# design.net
KiCad netlist of a schematic drawn in Altium Designer
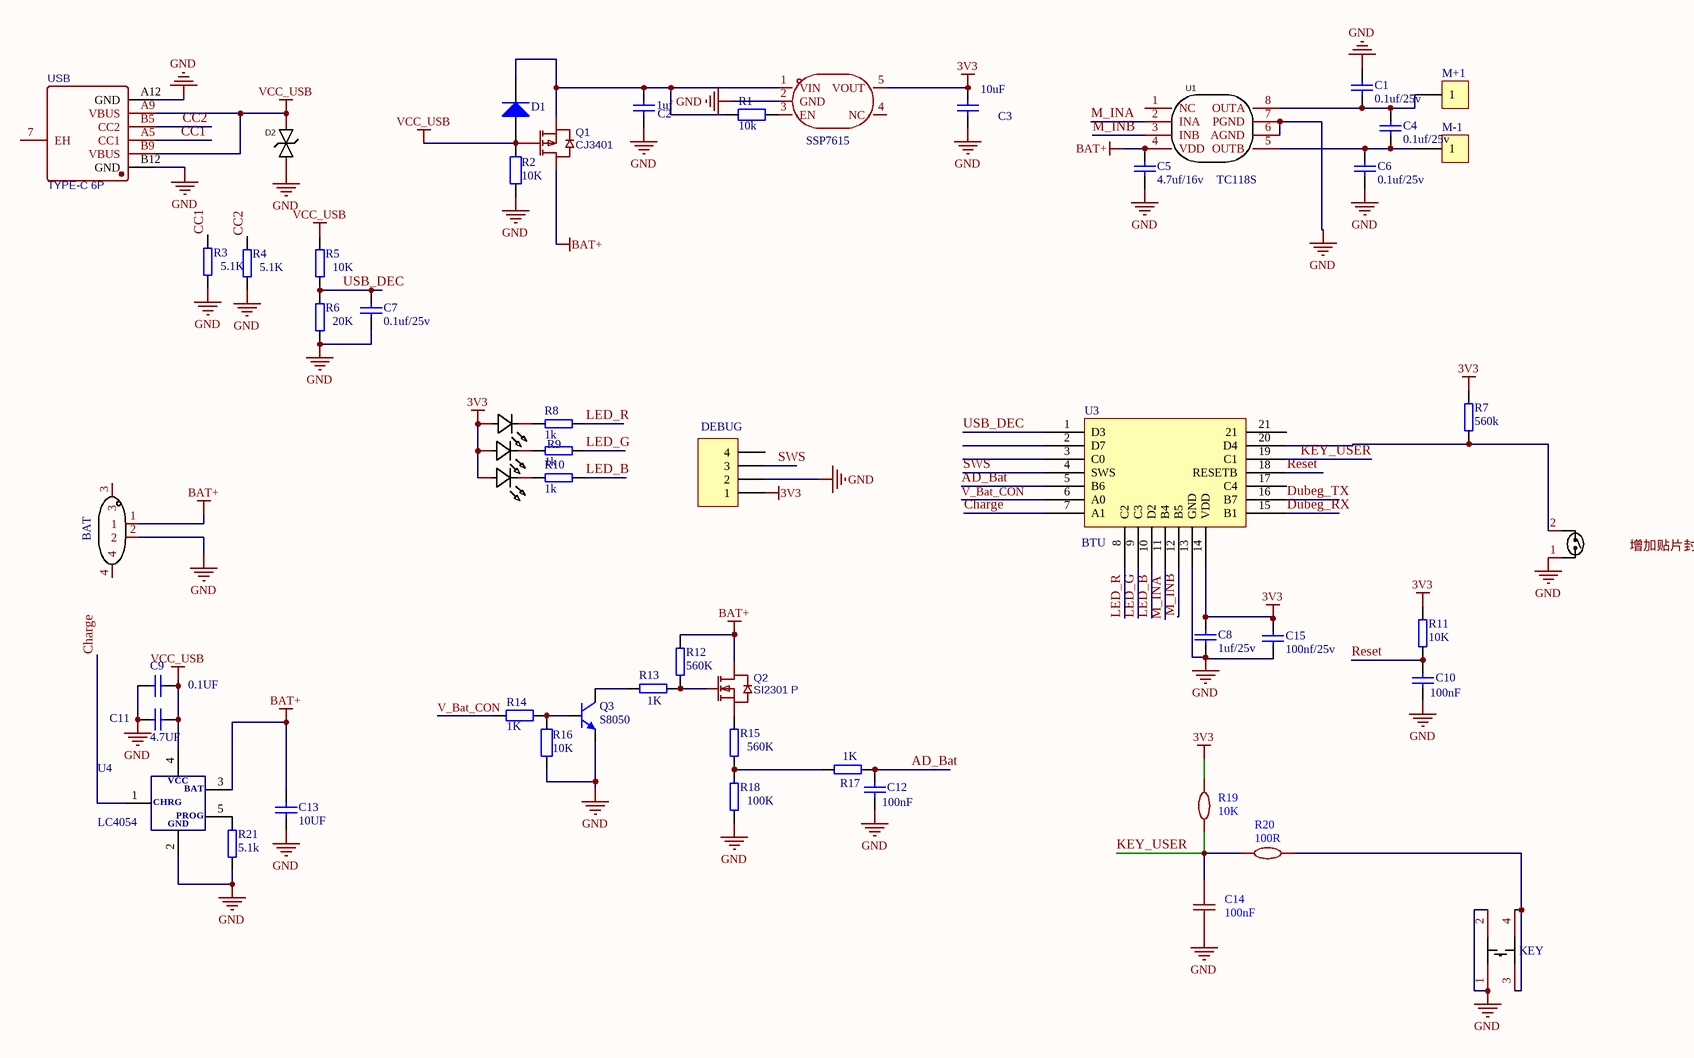
[diagram p0: 滚动足球球蓝牙款.SchDoc]

(export (version "E")
  (design (tool "Eeschema 10.0.6"))
  (components
    (comp (ref "C1")
      (value "0.1uf/25v")
      (footprint "0603_C")
      (description "Capacitor")
      (fields (field (name "PUBLISHER") "Altium Limited"))
      (libsource (lib "*") (part "Cap"))
    )
    (comp (ref "C2")
      (value "1uf")
      (footprint "0603_C")
      (description "无极电容")
      (libsource (lib "电容电阻电感保险") (part "Cap1"))
    )
    (comp (ref "C3")
      (value "10uF")
      (footprint "0603_C")
      (description "Capacitor")
      (fields (field (name "PUBLISHER") "Altium Limited"))
      (libsource (lib "*") (part "Cap"))
    )
    (comp (ref "C4")
      (value "0.1uf/25v")
      (footprint "0603_C")
      (description "Capacitor")
      (fields (field (name "PUBLISHER") "Altium Limited"))
      (libsource (lib "*") (part "Cap"))
    )
    (comp (ref "C5")
      (value "4.7uf/16v")
      (footprint "0805_C")
      (description "Capacitor")
      (fields (field (name "PUBLISHER") "Altium Limited"))
      (libsource (lib "*") (part "Cap"))
    )
    (comp (ref "C6")
      (value "0.1uf/25v")
      (footprint "0603_C")
      (description "Capacitor")
      (fields (field (name "PUBLISHER") "Altium Limited"))
      (libsource (lib "*") (part "Cap"))
    )
    (comp (ref "C7")
      (value "0.1uf/25v")
      (footprint "0603_C")
      (description "Capacitor")
      (fields (field (name "PUBLISHER") "Altium Limited"))
      (libsource (lib "*") (part "Cap"))
    )
    (comp (ref "C8")
      (value "1uf/25v")
      (footprint "0603_C")
      (description "Capacitor")
      (fields (field (name "PUBLISHER") "Altium Limited"))
      (libsource (lib "*") (part "Cap"))
    )
    (comp (ref "C9") (value "0.1UF") (footprint "0603_c") (libsource (lib "DIY") (part "CAP")))
    (comp (ref "C10") (value "100nF") (footprint "0603_C") (libsource (lib "DIY") (part "CAP")))
    (comp (ref "C11") (value "4.7UF") (footprint "0603_c") (libsource (lib "DIY") (part "CAP")))
    (comp (ref "C12") (value "100nF") (footprint "0603_C") (libsource (lib "DIY") (part "CAP")))
    (comp (ref "C13") (value "10UF") (footprint "0603_C") (libsource (lib "DIY") (part "CAP")))
    (comp (ref "C14")
      (value "100nF")
      (footprint "0603_c")
      (libsource (lib "altium-import") (part "root_1_CAP_0603_"))
    )
    (comp (ref "C15")
      (value "100nf/25v")
      (footprint "0603_C")
      (description "Capacitor")
      (fields (field (name "PUBLISHER") "Altium Limited"))
      (libsource (lib "*") (part "Cap"))
    )
    (comp (ref "CN1")
      (value "BAT")
      (footprint "CONN-SMD_1.25-2PWT")
      (fields (field (name "MANUFACTURER PART") "HC-1.25-2PLT"))
      (libsource (lib "altium-import") (part "root_0_mirrored_HC-1.25-2PLT_"))
    )
    (comp (ref "D1")
      (value "~")
      (footprint "SOD-123FL")
      (description "High Conductance Fast Diode")
      (fields (field (name "PUBLISHER") "Altium Limited"))
      (libsource (lib "Miscellaneous Devices") (part "Diode 1N4148"))
    )
    (comp (ref "D2")
      (value "SMF5.0CA_C726939")
      (footprint "SOD-123 双向")
      (fields (field (name "MANUFACTURER PART") "SMF5.0CA"))
      (libsource (lib "altium-import") (part "root_1_SMF5.0CA_C726939_"))
    )
    (comp (ref "K1")
      (value "KEY")
      (footprint "SW-SMD_4P-L4.5-W4.5-P3.00-LS7.0")
      (fields (field (name "MANUFACTURER PART") "TS-1002S-05026C"))
      (libsource (lib "altium-import") (part "root_1_TS-1002S-05026C_"))
    )
    (comp (ref "LED1")
      (value "S6-3528RGBTA")
      (footprint "LED-SMD-6P_S6-3528RGBTA")
      (libsource (lib "altium-import") (part "root_0_S6-3528RGBTA_"))
    )
    (comp (ref "M+1") (value "~") (footprint "PAD2") (libsource (lib "zzh-sch") (part "CON1")))
    (comp (ref "M-1") (value "~") (footprint "PAD2") (libsource (lib "zzh-sch") (part "CON1")))
    (comp (ref "P1")
      (value "DEBUG")
      (footprint "SIP4-2.54")
      (description "Header, 4-Pin")
      (fields (field (name "PUBLISHER") "Altium Limited"))
      (libsource (lib "Miscellaneous Connectors") (part "Header 4"))
    )
    (comp (ref "Q1")
      (value "CJ3401")
      (footprint "SOT-23")
      (fields (field (name "BOM_SUPPLIER PART") "C13799"))
      (libsource (lib "altium-import") (part "root_2_mirrored_CJ3401_"))
    )
    (comp (ref "Q2")
      (value "SI2301 P")
      (footprint "SOT-23")
      (fields
        (field (name "BOM_SUPPLIER PART") "C2890442")
        (field (name "BOM_MANUFACTURER PART") "JMTL3400A")
        (field (name "CONTRIBUTOR") "LCSC")
      )
      (libsource (lib "altium-import") (part "root_0_JMTL3400A_"))
    )
    (comp (ref "Q3")
      (value "S8050")
      (footprint "SOT-23(SOT-23-3)")
      (description "NPN三极管")
      (libsource (lib "二三极管mos可控硅") (part "NPN_sot23"))
    )
    (comp (ref "R1")
      (value "10k")
      (footprint "0603_R")
      (description "Resistor")
      (fields (field (name "PUBLISHER") "Altium Limited"))
      (libsource (lib "") (part "Res2_1"))
    )
    (comp (ref "R2")
      (value "10K")
      (footprint "0603_R")
      (description "Resistor")
      (fields (field (name "PUBLISHER") "Altium Limited"))
      (libsource (lib "") (part "Res2_2"))
    )
    (comp (ref "R3") (value "5.1K") (footprint "0603_R") (libsource (lib "DIY") (part "RES")))
    (comp (ref "R4") (value "5.1K") (footprint "0603_R") (libsource (lib "DIY") (part "RES")))
    (comp (ref "R5") (value "10K") (footprint "0603_R") (libsource (lib "DIY") (part "RES")))
    (comp (ref "R6") (value "20K") (footprint "0603_R") (libsource (lib "DIY") (part "RES")))
    (comp (ref "R7") (value "560k") (footprint "0603_R") (libsource (lib "DIY") (part "RES")))
    (comp (ref "R8") (value "1k") (footprint "0603_R") (libsource (lib "DIY") (part "RES")))
    (comp (ref "R9") (value "1k") (footprint "0603_R") (libsource (lib "DIY") (part "RES")))
    (comp (ref "R10") (value "1k") (footprint "0603_R") (libsource (lib "DIY") (part "RES")))
    (comp (ref "R11") (value "10K") (footprint "0603_R") (libsource (lib "DIY") (part "RES")))
    (comp (ref "R12") (value "560K") (footprint "0603_R") (libsource (lib "") (part "RES_1")))
    (comp (ref "R13") (value "1K") (footprint "0603_R") (libsource (lib "*") (part "RES")))
    (comp (ref "R14")
      (value "1K")
      (footprint "0603_r")
      (description "Resistor")
      (fields (field (name "PUBLISHER") "Altium Limited"))
      (libsource (lib "*") (part "Res2"))
    )
    (comp (ref "R15") (value "560K") (footprint "0603_R") (libsource (lib "DIY") (part "RES")))
    (comp (ref "R16")
      (value "10K")
      (footprint "0603_r")
      (description "Resistor")
      (fields (field (name "PUBLISHER") "Altium Limited"))
      (libsource (lib "") (part "Res2_1"))
    )
    (comp (ref "R17") (value "1K") (footprint "0603_R") (libsource (lib "DIY") (part "RES")))
    (comp (ref "R18") (value "100K") (footprint "0603_R") (libsource (lib "DIY") (part "RES")))
    (comp (ref "R19")
      (value "10K")
      (footprint "0603_R")
      (libsource (lib "altium-import") (part "root_1_Res_0603_"))
    )
    (comp (ref "R20")
      (value "100R")
      (footprint "0603_R")
      (libsource (lib "altium-import") (part "root_2_Res_0603_"))
    )
    (comp (ref "R21") (value "5.1k") (footprint "0603_R") (libsource (lib "DIY") (part "RES")))
    (comp (ref "SW1")
      (value "SW-18010P")
      (footprint "SMD-X160")
      (libsource (lib "altium-import") (part "root_0_SW-18010P_"))
    )
    (comp (ref "U1")
      (value "TC118S")
      (footprint "SOP8")
      (libsource (lib "altium-import") (part "root_0_TC118S_"))
    )
    (comp (ref "U2")
      (value "SSP7615")
      (footprint "SOT-23-5")
      (libsource (lib "altium-import") (part "root_0_SSP7615-33M5R_"))
    )
    (comp (ref "U3") (value "BTU") (footprint "BTU") (libsource (lib "MyLib") (part "BTU")))
    (comp (ref "U4") (value "LC4054") (footprint "SOT-23-5") (libsource (lib "DIY") (part "LTC4054")))
    (comp (ref "USB")
      (value "TYPE-C 6P")
      (footprint "TPYE-C-6")
      (fields (field (name "BOM_SUPPLIER PART") "C456012") (field (name "CONTRIBUTOR") "LCSC"))
      (libsource (lib "altium-import") (part "root_2_TYPE-C 6P_"))
    )
  )
  (nets
    (net (code "1") (name "/AD_Bat") (class "Default")
      (node (ref "C12") (pin "2") (pintype "passive"))
      (node (ref "R17") (pin "1") (pinfunction "1_1") (pintype "passive"))
      (node (ref "U3") (pin "5") (pinfunction "B6_5") (pintype "passive"))
    )
    (net (code "2") (name "/CC1") (class "Default")
      (node (ref "R3") (pin "1") (pinfunction "1_1") (pintype "passive"))
      (node (ref "USB") (pin "A5") (pinfunction "CC1_A5") (pintype "passive"))
    )
    (net (code "3") (name "/CC2") (class "Default")
      (node (ref "R4") (pin "1") (pinfunction "1_1") (pintype "passive"))
      (node (ref "USB") (pin "B5") (pinfunction "CC2_B5") (pintype "passive"))
    )
    (net (code "4") (name "/Charge") (class "Default")
      (node (ref "U3") (pin "7") (pinfunction "A1_7") (pintype "passive"))
      (node (ref "U4") (pin "1") (pinfunction "1_1") (pintype "passive"))
    )
    (net (code "5") (name "/Dubeg_RX") (class "Default")
      (node (ref "U3") (pin "15") (pinfunction "B1_15") (pintype "passive"))
    )
    (net (code "6") (name "/Dubeg_TX") (class "Default")
      (node (ref "U3") (pin "16") (pinfunction "B7_16") (pintype "passive"))
    )
    (net (code "7") (name "/KEY_USER") (class "Default")
      (node (ref "C14") (pin "2") (pinfunction "2_2") (pintype "passive"))
      (node (ref "R19") (pin "1") (pinfunction "1_1") (pintype "passive"))
      (node (ref "R20") (pin "2") (pinfunction "2_2") (pintype "passive"))
      (node (ref "U3") (pin "19") (pinfunction "C1_19") (pintype "passive"))
    )
    (net (code "8") (name "/LED_B") (class "Default")
      (node (ref "R10") (pin "2") (pinfunction "2_2") (pintype "passive"))
      (node (ref "U3") (pin "10") (pinfunction "D2_10") (pintype "passive"))
    )
    (net (code "9") (name "/LED_G") (class "Default")
      (node (ref "R9") (pin "2") (pinfunction "2_2") (pintype "passive"))
      (node (ref "U3") (pin "9") (pinfunction "C3_9") (pintype "passive"))
    )
    (net (code "10") (name "/LED_R") (class "Default")
      (node (ref "R8") (pin "2") (pinfunction "2_2") (pintype "passive"))
      (node (ref "U3") (pin "8") (pinfunction "C2_8") (pintype "passive"))
    )
    (net (code "11") (name "/M_INA") (class "Default")
      (node (ref "U1") (pin "2") (pinfunction "INA_2") (pintype "passive"))
      (node (ref "U3") (pin "11") (pinfunction "B4_11") (pintype "passive"))
    )
    (net (code "12") (name "/M_INB") (class "Default")
      (node (ref "U1") (pin "3") (pinfunction "INB_3") (pintype "passive"))
      (node (ref "U3") (pin "12") (pinfunction "B5_12") (pintype "passive"))
    )
    (net (code "13") (name "/Reset") (class "Default")
      (node (ref "C10") (pin "2") (pintype "passive"))
      (node (ref "R11") (pin "2") (pinfunction "2_2") (pintype "passive"))
      (node (ref "U3") (pin "18") (pinfunction "RESETB_18") (pintype "passive"))
    )
    (net (code "14") (name "/SWS") (class "Default")
      (node (ref "P1") (pin "3") (pinfunction "3_3") (pintype "passive"))
      (node (ref "U3") (pin "4") (pinfunction "SWS_4") (pintype "passive"))
    )
    (net (code "15") (name "/USB_DEC") (class "Default")
      (node (ref "C7") (pin "2") (pinfunction "2_2") (pintype "passive"))
      (node (ref "R5") (pin "2") (pinfunction "2_2") (pintype "passive"))
      (node (ref "R6") (pin "1") (pinfunction "1_1") (pintype "passive"))
      (node (ref "U3") (pin "1") (pinfunction "D3_1") (pintype "passive"))
    )
    (net (code "16") (name "/V_Bat_CON") (class "Default")
      (node (ref "R14") (pin "2") (pinfunction "2_2") (pintype "passive"))
      (node (ref "U3") (pin "6") (pinfunction "A0_6") (pintype "passive"))
    )
    (net (code "18") (name "3V3") (class "Default")
      (node (ref "C15") (pin "2") (pinfunction "2_2") (pintype "passive"))
      (node (ref "C3") (pin "2") (pinfunction "2_2") (pintype "passive"))
      (node (ref "C8") (pin "2") (pinfunction "2_2") (pintype "passive"))
      (node (ref "LED1") (pin "4") (pinfunction "4_4") (pintype "passive"))
      (node (ref "LED1") (pin "5") (pinfunction "5_5") (pintype "passive"))
      (node (ref "LED1") (pin "6") (pinfunction "6_6") (pintype "passive"))
      (node (ref "P1") (pin "1") (pinfunction "1_1") (pintype "passive"))
      (node (ref "R11") (pin "1") (pinfunction "1_1") (pintype "passive"))
      (node (ref "R19") (pin "2") (pinfunction "2_2") (pintype "passive"))
      (node (ref "R7") (pin "2") (pinfunction "2_2") (pintype "passive"))
      (node (ref "U2") (pin "5") (pinfunction "VOUT_5") (pintype "passive"))
      (node (ref "U3") (pin "14") (pinfunction "VDD_14") (pintype "passive"))
    )
    (net (code "19") (name "BAT+") (class "Default")
      (node (ref "C13") (pin "2") (pintype "passive"))
      (node (ref "C5") (pin "1") (pinfunction "1_1") (pintype "passive"))
      (node (ref "CN1") (pin "1") (pinfunction "1_1") (pintype "passive"))
      (node (ref "Q1") (pin "3") (pinfunction "D_3") (pintype "passive"))
      (node (ref "Q2") (pin "2") (pinfunction "D_2") (pintype "passive"))
      (node (ref "R12") (pin "1") (pintype "passive"))
      (node (ref "U1") (pin "4") (pinfunction "VDD_4") (pintype "passive"))
      (node (ref "U4") (pin "3") (pinfunction "3_3") (pintype "passive"))
    )
    (net (code "20") (name "GND") (class "Default")
      (node (ref "C1") (pin "2") (pinfunction "2_2") (pintype "passive"))
      (node (ref "C10") (pin "1") (pintype "passive"))
      (node (ref "C11") (pin "1") (pintype "passive"))
      (node (ref "C12") (pin "1") (pintype "passive"))
      (node (ref "C13") (pin "1") (pintype "passive"))
      (node (ref "C14") (pin "1") (pinfunction "1_1") (pintype "passive"))
      (node (ref "C15") (pin "1") (pinfunction "1_1") (pintype "passive"))
      (node (ref "C2") (pin "1") (pinfunction "1_1") (pintype "passive"))
      (node (ref "C3") (pin "1") (pinfunction "1_1") (pintype "passive"))
      (node (ref "C5") (pin "2") (pinfunction "2_2") (pintype "passive"))
      (node (ref "C6") (pin "1") (pinfunction "1_1") (pintype "passive"))
      (node (ref "C7") (pin "1") (pinfunction "1_1") (pintype "passive"))
      (node (ref "C8") (pin "1") (pinfunction "1_1") (pintype "passive"))
      (node (ref "C9") (pin "1") (pintype "passive"))
      (node (ref "CN1") (pin "2") (pinfunction "2_2") (pintype "passive"))
      (node (ref "D2") (pin "1") (pinfunction "1_1") (pintype "passive"))
      (node (ref "K1") (pin "1") (pinfunction "1_1") (pintype "passive"))
      (node (ref "K1") (pin "2") (pinfunction "2_2") (pintype "passive"))
      (node (ref "P1") (pin "2") (pinfunction "2_2") (pintype "passive"))
      (node (ref "Q3") (pin "2") (pinfunction "E_2") (pintype "passive"))
      (node (ref "R16") (pin "1") (pinfunction "1_1") (pintype "passive"))
      (node (ref "R18") (pin "2") (pinfunction "2_2") (pintype "passive"))
      (node (ref "R2") (pin "1") (pinfunction "1_1") (pintype "passive"))
      (node (ref "R21") (pin "1") (pinfunction "1_1") (pintype "passive"))
      (node (ref "R3") (pin "2") (pinfunction "2_2") (pintype "passive"))
      (node (ref "R4") (pin "2") (pinfunction "2_2") (pintype "passive"))
      (node (ref "R6") (pin "2") (pinfunction "2_2") (pintype "passive"))
      (node (ref "SW1") (pin "1") (pinfunction "1_1") (pintype "passive"))
      (node (ref "U1") (pin "6") (pinfunction "AGND_6") (pintype "passive"))
      (node (ref "U1") (pin "7") (pinfunction "PGND_7") (pintype "passive"))
      (node (ref "U2") (pin "2") (pinfunction "GND_2") (pintype "passive"))
      (node (ref "U3") (pin "13") (pinfunction "GND_13") (pintype "passive"))
      (node (ref "U4") (pin "2") (pinfunction "2_2") (pintype "passive"))
      (node (ref "USB") (pin "A12") (pinfunction "GND_A12") (pintype "passive"))
      (node (ref "USB") (pin "B12") (pinfunction "GND_B12") (pintype "passive"))
    )
    (net (code "21") (name "Net-(D1-K)") (class "Default")
      (node (ref "C2") (pin "2") (pinfunction "2_2") (pintype "passive"))
      (node (ref "D1") (pin "2") (pinfunction "K_2") (pintype "passive"))
      (node (ref "Q1") (pin "2") (pinfunction "S_2") (pintype "passive"))
      (node (ref "R1") (pin "1") (pinfunction "1_1") (pintype "passive"))
      (node (ref "U2") (pin "1") (pinfunction "VIN_1") (pintype "passive"))
    )
    (net (code "22") (name "Net-(K1-Pad3)") (class "Default")
      (node (ref "K1") (pin "3") (pinfunction "3_3") (pintype "passive"))
      (node (ref "K1") (pin "4") (pinfunction "4_4") (pintype "passive"))
      (node (ref "R20") (pin "1") (pinfunction "1_1") (pintype "passive"))
    )
    (net (code "23") (name "Net-(LED1-Pad1)") (class "Default")
      (node (ref "LED1") (pin "1") (pinfunction "1_1") (pintype "passive"))
      (node (ref "R10") (pin "1") (pinfunction "1_1") (pintype "passive"))
    )
    (net (code "24") (name "Net-(LED1-Pad2)") (class "Default")
      (node (ref "LED1") (pin "2") (pinfunction "2_2") (pintype "passive"))
      (node (ref "R9") (pin "1") (pinfunction "1_1") (pintype "passive"))
    )
    (net (code "25") (name "Net-(LED1-Pad3)") (class "Default")
      (node (ref "LED1") (pin "3") (pinfunction "3_3") (pintype "passive"))
      (node (ref "R8") (pin "1") (pinfunction "1_1") (pintype "passive"))
    )
    (net (code "26") (name "Net-(Q2-G)") (class "Default")
      (node (ref "Q2") (pin "1") (pinfunction "G_1") (pintype "passive"))
      (node (ref "R12") (pin "2") (pintype "passive"))
      (node (ref "R13") (pin "1") (pintype "passive"))
    )
    (net (code "27") (name "Net-(Q2-S)") (class "Default")
      (node (ref "Q2") (pin "3") (pinfunction "S_3") (pintype "passive"))
      (node (ref "R15") (pin "1") (pinfunction "1_1") (pintype "passive"))
    )
    (net (code "28") (name "Net-(Q3-B)") (class "Default")
      (node (ref "Q3") (pin "1") (pinfunction "B_1") (pintype "passive"))
      (node (ref "R14") (pin "1") (pinfunction "1_1") (pintype "passive"))
      (node (ref "R16") (pin "2") (pinfunction "2_2") (pintype "passive"))
    )
    (net (code "29") (name "Net-(Q3-C)") (class "Default")
      (node (ref "Q3") (pin "3") (pinfunction "C_3") (pintype "passive"))
      (node (ref "R13") (pin "2") (pintype "passive"))
    )
    (net (code "30") (name "Net-(R15-Pad2)") (class "Default")
      (node (ref "R15") (pin "2") (pinfunction "2_2") (pintype "passive"))
      (node (ref "R17") (pin "2") (pinfunction "2_2") (pintype "passive"))
      (node (ref "R18") (pin "1") (pinfunction "1_1") (pintype "passive"))
    )
    (net (code "31") (name "Net-(R21-Pad2)") (class "Default")
      (node (ref "R21") (pin "2") (pinfunction "2_2") (pintype "passive"))
      (node (ref "U4") (pin "5") (pinfunction "5_5") (pintype "passive"))
    )
    (net (code "32") (name "Net-(U1-OUTA)") (class "Default")
      (node (ref "C1") (pin "1") (pinfunction "1_1") (pintype "passive"))
      (node (ref "C4") (pin "2") (pinfunction "2_2") (pintype "passive"))
      (node (ref "M+1") (pin "1") (pinfunction "1_1") (pintype "passive"))
      (node (ref "U1") (pin "8") (pinfunction "OUTA_8") (pintype "passive"))
    )
    (net (code "33") (name "Net-(U1-OUTB)") (class "Default")
      (node (ref "C4") (pin "1") (pinfunction "1_1") (pintype "passive"))
      (node (ref "C6") (pin "2") (pinfunction "2_2") (pintype "passive"))
      (node (ref "M-1") (pin "1") (pinfunction "1_1") (pintype "passive"))
      (node (ref "U1") (pin "5") (pinfunction "OUTB_5") (pintype "passive"))
    )
    (net (code "34") (name "Net-(U2-EN)") (class "Default")
      (node (ref "R1") (pin "2") (pinfunction "2_2") (pintype "passive"))
      (node (ref "U2") (pin "3") (pinfunction "EN_3") (pintype "passive"))
    )
    (net (code "35") (name "Net-(U3-D4)") (class "Default")
      (node (ref "R7") (pin "1") (pinfunction "1_1") (pintype "passive"))
      (node (ref "SW1") (pin "2") (pinfunction "2_2") (pintype "passive"))
      (node (ref "U3") (pin "20") (pinfunction "D4_20") (pintype "passive"))
    )
    (net (code "36") (name "VCC_USB") (class "Default")
      (node (ref "C11") (pin "2") (pintype "passive"))
      (node (ref "C9") (pin "2") (pintype "passive"))
      (node (ref "D1") (pin "1") (pinfunction "A_1") (pintype "passive"))
      (node (ref "D2") (pin "2") (pinfunction "2_2") (pintype "passive"))
      (node (ref "Q1") (pin "1") (pinfunction "G_1") (pintype "passive"))
      (node (ref "R2") (pin "2") (pinfunction "2_2") (pintype "passive"))
      (node (ref "R5") (pin "1") (pinfunction "1_1") (pintype "passive"))
      (node (ref "U4") (pin "4") (pinfunction "4_4") (pintype "passive"))
      (node (ref "USB") (pin "A9") (pinfunction "VBUS_A9") (pintype "passive"))
      (node (ref "USB") (pin "B9") (pinfunction "VBUS_B9") (pintype "passive"))
    )
    (net (code "37") (name "unconnected-(CN1-Pad3)") (class "Default")
      (node (ref "CN1") (pin "3") (pinfunction "3_3") (pintype "passive"))
    )
    (net (code "38") (name "unconnected-(CN1-Pad4)") (class "Default")
      (node (ref "CN1") (pin "4") (pinfunction "4_4") (pintype "passive"))
    )
    (net (code "39") (name "unconnected-(P1-Pad4)") (class "Default")
      (node (ref "P1") (pin "4") (pinfunction "4_4") (pintype "passive"))
    )
    (net (code "40") (name "unconnected-(U1-NC-Pad1)") (class "Default")
      (node (ref "U1") (pin "1") (pinfunction "NC_1") (pintype "passive"))
    )
    (net (code "41") (name "unconnected-(U2-NC-Pad4)") (class "Default")
      (node (ref "U2") (pin "4") (pinfunction "NC_4") (pintype "passive"))
    )
    (net (code "42") (name "unconnected-(U3-C0-Pad3)") (class "Default")
      (node (ref "U3") (pin "3") (pinfunction "C0_3") (pintype "passive"))
    )
    (net (code "43") (name "unconnected-(U3-C4-Pad17)") (class "Default")
      (node (ref "U3") (pin "17") (pinfunction "C4_17") (pintype "passive"))
    )
    (net (code "44") (name "unconnected-(U3-D7-Pad2)") (class "Default")
      (node (ref "U3") (pin "2") (pinfunction "D7_2") (pintype "passive"))
    )
    (net (code "45") (name "unconnected-(U3-Pad21)") (class "Default")
      (node (ref "U3") (pin "21") (pinfunction "21_21") (pintype "passive"))
    )
    (net (code "46") (name "unconnected-(USB-EH-Pad7)") (class "Default")
      (node (ref "USB") (pin "7") (pinfunction "EH_7") (pintype "passive"))
    )
  )
)
